# RGB_i2c_v1.net
KiCad netlist of a schematic drawn in EAGLE
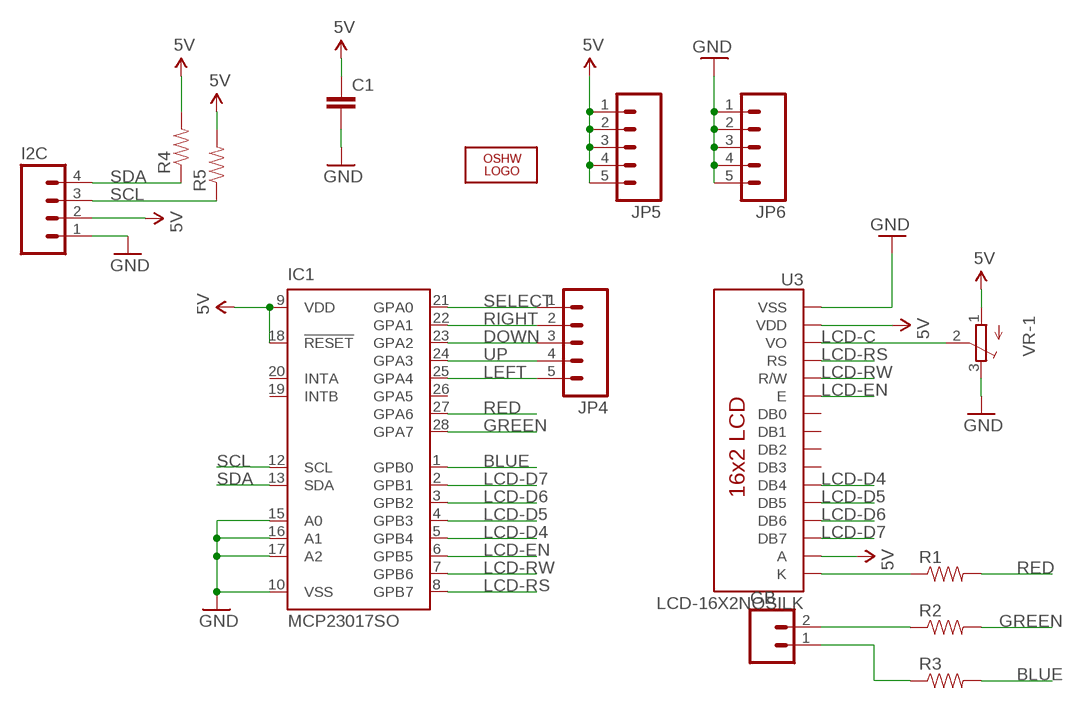
[diagram p0: schematic, sheet 1]

(export (version "E")
  (design (tool "Eeschema 10.0.6"))
  (components
    (comp (ref "C1")
      (value "CAP0805")
      (footprint "eagle-import:0805")
      (libsource (lib "eagle-import") (part "CAP0805"))
    )
    (comp (ref "GB")
      (value "M02LOCK")
      (footprint "eagle-import:1X02_LOCK")
      (libsource (lib "eagle-import") (part "M02LOCK"))
    )
    (comp (ref "I2C")
      (value "M04LOCK")
      (footprint "eagle-import:1X04_LOCK")
      (libsource (lib "eagle-import") (part "M04LOCK"))
    )
    (comp (ref "IC1")
      (value "MCP23017SO")
      (footprint "eagle-import:SO28W")
      (libsource (lib "eagle-import") (part "MCP23017SO"))
    )
    (comp (ref "JP4")
      (value "M05LOCK")
      (footprint "eagle-import:1X05_LOCK")
      (libsource (lib "eagle-import") (part "M05LOCK"))
    )
    (comp (ref "JP5")
      (value "M05LOCK")
      (footprint "eagle-import:1X05_LOCK")
      (libsource (lib "eagle-import") (part "M05LOCK"))
    )
    (comp (ref "JP6")
      (value "M05LOCK")
      (footprint "eagle-import:1X05_LOCK")
      (libsource (lib "eagle-import") (part "M05LOCK"))
    )
    (comp (ref "LOGO2")
      (value "OSHW_LOGO_10MILX0350-NT")
      (footprint "eagle-import:OSHW_10X350_NOTEXT")
      (libsource (lib "eagle-import") (part "OSHW_LOGO_10MILX0350-NT"))
    )
    (comp (ref "R1")
      (value "RESISTOR0805-RES")
      (footprint "eagle-import:0805")
      (libsource (lib "eagle-import") (part "RESISTOR0805-RES"))
    )
    (comp (ref "R2")
      (value "RESISTOR0805-RES")
      (footprint "eagle-import:0805")
      (libsource (lib "eagle-import") (part "RESISTOR0805-RES"))
    )
    (comp (ref "R3")
      (value "RESISTOR0805-RES")
      (footprint "eagle-import:0805")
      (libsource (lib "eagle-import") (part "RESISTOR0805-RES"))
    )
    (comp (ref "R4")
      (value "RESISTOR0805-RES")
      (footprint "eagle-import:0805")
      (libsource (lib "eagle-import") (part "RESISTOR0805-RES"))
    )
    (comp (ref "R5")
      (value "RESISTOR0805-RES")
      (footprint "eagle-import:0805")
      (libsource (lib "eagle-import") (part "RESISTOR0805-RES"))
    )
    (comp (ref "U3")
      (value "LCD-16X2NOSILK")
      (footprint "eagle-import:LCD-16X2_NOSILK")
      (libsource (lib "eagle-import") (part "LCD-16X2NOSILK"))
    )
    (comp (ref "VR-1")
      (value "TRIMPOTTC33X")
      (footprint "eagle-import:TC33X")
      (libsource (lib "eagle-import") (part "TRIMPOTTC33X"))
    )
  )
  (nets
    (net (code "1") (name "/BLUE") (class "Default")
      (node (ref "IC1") (pin "1") (pinfunction "GPB0_1") (pintype "bidirectional"))
      (node (ref "R3") (pin "2") (pinfunction "2_2") (pintype "passive"))
    )
    (net (code "2") (name "/DOWN") (class "Default")
      (node (ref "IC1") (pin "23") (pinfunction "GPA2_23") (pintype "bidirectional"))
      (node (ref "JP4") (pin "3") (pinfunction "3_3") (pintype "passive"))
    )
    (net (code "3") (name "/GREEN") (class "Default")
      (node (ref "IC1") (pin "28") (pinfunction "GPA7_28") (pintype "bidirectional"))
      (node (ref "R2") (pin "2") (pinfunction "2_2") (pintype "passive"))
    )
    (net (code "4") (name "/LCD-C") (class "Default")
      (node (ref "U3") (pin "3") (pinfunction "VO_3") (pintype "bidirectional"))
      (node (ref "VR-1") (pin "2") (pinfunction "S_2") (pintype "passive"))
    )
    (net (code "5") (name "/LCD-D4") (class "Default")
      (node (ref "IC1") (pin "5") (pinfunction "GPB4_5") (pintype "bidirectional"))
      (node (ref "U3") (pin "11") (pinfunction "DB4_11") (pintype "bidirectional"))
    )
    (net (code "6") (name "/LCD-D5") (class "Default")
      (node (ref "IC1") (pin "4") (pinfunction "GPB3_4") (pintype "bidirectional"))
      (node (ref "U3") (pin "12") (pinfunction "DB5_12") (pintype "bidirectional"))
    )
    (net (code "7") (name "/LCD-D6") (class "Default")
      (node (ref "IC1") (pin "3") (pinfunction "GPB2_3") (pintype "bidirectional"))
      (node (ref "U3") (pin "13") (pinfunction "DB6_13") (pintype "bidirectional"))
    )
    (net (code "8") (name "/LCD-D7") (class "Default")
      (node (ref "IC1") (pin "2") (pinfunction "GPB1_2") (pintype "bidirectional"))
      (node (ref "U3") (pin "14") (pinfunction "DB7_14") (pintype "bidirectional"))
    )
    (net (code "9") (name "/LCD-EN") (class "Default")
      (node (ref "IC1") (pin "6") (pinfunction "GPB5_6") (pintype "bidirectional"))
      (node (ref "U3") (pin "6") (pinfunction "E_6") (pintype "input"))
    )
    (net (code "10") (name "/LCD-RS") (class "Default")
      (node (ref "IC1") (pin "8") (pinfunction "GPB7_8") (pintype "bidirectional"))
      (node (ref "U3") (pin "4") (pinfunction "RS_4") (pintype "input"))
    )
    (net (code "11") (name "/LCD-RW") (class "Default")
      (node (ref "IC1") (pin "7") (pinfunction "GPB6_7") (pintype "bidirectional"))
      (node (ref "U3") (pin "5") (pinfunction "R/W_5") (pintype "input"))
    )
    (net (code "12") (name "/LEFT") (class "Default")
      (node (ref "IC1") (pin "25") (pinfunction "GPA4_25") (pintype "bidirectional"))
      (node (ref "JP4") (pin "5") (pinfunction "5_5") (pintype "passive"))
    )
    (net (code "13") (name "/RED") (class "Default")
      (node (ref "IC1") (pin "27") (pinfunction "GPA6_27") (pintype "bidirectional"))
      (node (ref "R1") (pin "2") (pinfunction "2_2") (pintype "passive"))
    )
    (net (code "14") (name "/RIGHT") (class "Default")
      (node (ref "IC1") (pin "22") (pinfunction "GPA1_22") (pintype "bidirectional"))
      (node (ref "JP4") (pin "2") (pinfunction "2_2") (pintype "passive"))
    )
    (net (code "15") (name "/SCL") (class "Default")
      (node (ref "I2C") (pin "3") (pinfunction "3_3") (pintype "passive"))
      (node (ref "IC1") (pin "12") (pinfunction "SCL_12") (pintype "input"))
      (node (ref "R5") (pin "1") (pinfunction "1_1") (pintype "passive"))
    )
    (net (code "16") (name "/SDA") (class "Default")
      (node (ref "I2C") (pin "4") (pinfunction "4_4") (pintype "passive"))
      (node (ref "IC1") (pin "13") (pinfunction "SDA_13") (pintype "bidirectional"))
      (node (ref "R4") (pin "1") (pinfunction "1_1") (pintype "passive"))
    )
    (net (code "17") (name "/SELECT") (class "Default")
      (node (ref "IC1") (pin "21") (pinfunction "GPA0_21") (pintype "bidirectional"))
      (node (ref "JP4") (pin "1") (pinfunction "1_1") (pintype "passive"))
    )
    (net (code "18") (name "/UP") (class "Default")
      (node (ref "IC1") (pin "24") (pinfunction "GPA3_24") (pintype "bidirectional"))
      (node (ref "JP4") (pin "4") (pinfunction "4_4") (pintype "passive"))
    )
    (net (code "19") (name "5V") (class "Default")
      (node (ref "C1") (pin "1") (pinfunction "1_1") (pintype "passive"))
      (node (ref "I2C") (pin "2") (pinfunction "2_2") (pintype "passive"))
      (node (ref "IC1") (pin "18") (pinfunction "~{RESET}_18") (pintype "input"))
      (node (ref "IC1") (pin "9") (pinfunction "VDD_9") (pintype "power_in"))
      (node (ref "JP5") (pin "1") (pinfunction "1_1") (pintype "passive"))
      (node (ref "JP5") (pin "2") (pinfunction "2_2") (pintype "passive"))
      (node (ref "JP5") (pin "3") (pinfunction "3_3") (pintype "passive"))
      (node (ref "JP5") (pin "4") (pinfunction "4_4") (pintype "passive"))
      (node (ref "JP5") (pin "5") (pinfunction "5_5") (pintype "passive"))
      (node (ref "R4") (pin "2") (pinfunction "2_2") (pintype "passive"))
      (node (ref "R5") (pin "2") (pinfunction "2_2") (pintype "passive"))
      (node (ref "U3") (pin "15") (pinfunction "A_15") (pintype "power_in"))
      (node (ref "U3") (pin "2") (pinfunction "VDD_2") (pintype "power_in"))
      (node (ref "VR-1") (pin "1") (pinfunction "A_1") (pintype "passive"))
    )
    (net (code "20") (name "GND") (class "Default")
      (node (ref "C1") (pin "2") (pinfunction "2_2") (pintype "passive"))
      (node (ref "I2C") (pin "1") (pinfunction "1_1") (pintype "passive"))
      (node (ref "IC1") (pin "10") (pinfunction "VSS_10") (pintype "power_in"))
      (node (ref "IC1") (pin "15") (pinfunction "A0_15") (pintype "input"))
      (node (ref "IC1") (pin "16") (pinfunction "A1_16") (pintype "input"))
      (node (ref "IC1") (pin "17") (pinfunction "A2_17") (pintype "input"))
      (node (ref "JP6") (pin "1") (pinfunction "1_1") (pintype "passive"))
      (node (ref "JP6") (pin "2") (pinfunction "2_2") (pintype "passive"))
      (node (ref "JP6") (pin "3") (pinfunction "3_3") (pintype "passive"))
      (node (ref "JP6") (pin "4") (pinfunction "4_4") (pintype "passive"))
      (node (ref "JP6") (pin "5") (pinfunction "5_5") (pintype "passive"))
      (node (ref "U3") (pin "1") (pinfunction "VSS_1") (pintype "power_in"))
      (node (ref "VR-1") (pin "3") (pinfunction "E_3") (pintype "passive"))
    )
    (net (code "21") (name "Net-(GB-Pad1)") (class "Default")
      (node (ref "GB") (pin "1") (pinfunction "1_1") (pintype "passive"))
      (node (ref "R3") (pin "1") (pinfunction "1_1") (pintype "passive"))
    )
    (net (code "22") (name "Net-(GB-Pad2)") (class "Default")
      (node (ref "GB") (pin "2") (pinfunction "2_2") (pintype "passive"))
      (node (ref "R2") (pin "1") (pinfunction "1_1") (pintype "passive"))
    )
    (net (code "23") (name "Net-(U3-K)") (class "Default")
      (node (ref "R1") (pin "1") (pinfunction "1_1") (pintype "passive"))
      (node (ref "U3") (pin "16") (pinfunction "K_16") (pintype "power_in"))
    )
    (net (code "24") (name "unconnected-(IC1-GPA5-Pad26)") (class "Default")
      (node (ref "IC1") (pin "26") (pinfunction "GPA5_26") (pintype "bidirectional"))
    )
    (net (code "25") (name "unconnected-(IC1-INTA-Pad20)") (class "Default")
      (node (ref "IC1") (pin "20") (pinfunction "INTA_20") (pintype "output"))
    )
    (net (code "26") (name "unconnected-(IC1-INTB-Pad19)") (class "Default")
      (node (ref "IC1") (pin "19") (pinfunction "INTB_19") (pintype "output"))
    )
    (net (code "27") (name "unconnected-(U3-DB0-Pad7)") (class "Default")
      (node (ref "U3") (pin "7") (pinfunction "DB0_7") (pintype "bidirectional"))
    )
    (net (code "28") (name "unconnected-(U3-DB1-Pad8)") (class "Default")
      (node (ref "U3") (pin "8") (pinfunction "DB1_8") (pintype "bidirectional"))
    )
    (net (code "29") (name "unconnected-(U3-DB2-Pad9)") (class "Default")
      (node (ref "U3") (pin "9") (pinfunction "DB2_9") (pintype "bidirectional"))
    )
    (net (code "30") (name "unconnected-(U3-DB3-Pad10)") (class "Default")
      (node (ref "U3") (pin "10") (pinfunction "DB3_10") (pintype "bidirectional"))
    )
  )
)
